# Power_Protection.net
KiCad netlist of a schematic drawn in Altium Designer
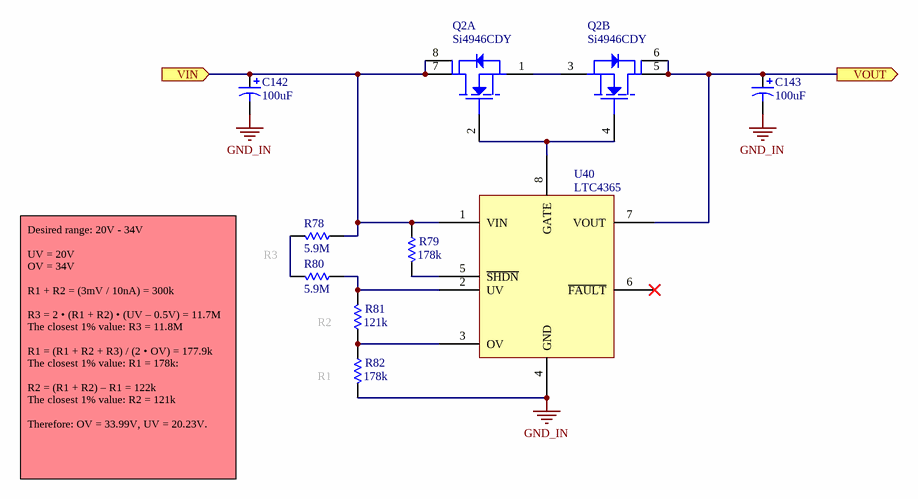
[diagram p0: Power_Protection.SchDoc]

(export (version "E")
  (design (tool "Eeschema 10.0.6"))
  (components
    (comp (ref "C142")
      (value "100uF")
      (footprint "AMDC:CAP - UWT1V101MCL1GS")
      (description "Polarized Capacitor (Radial)")
      (fields (field (name "Comment") "Cap Pol1"))
      (libsource (lib "Miscellaneous Devices") (part "Cap Pol1"))
    )
    (comp (ref "C143")
      (value "100uF")
      (footprint "AMDC:CAP - UWT1V101MCL1GS")
      (description "Polarized Capacitor (Radial)")
      (fields (field (name "Comment") "Cap Pol1"))
      (libsource (lib "Miscellaneous Devices") (part "Cap Pol1"))
    )
    (comp (ref "Q2")
      (value "Si4946CDY")
      (footprint "AMDC:SOIC127P600X175-8N")
      (description "MOSFET N-CHAN DUAL 60V SO-8")
      (libsource (lib "AMDC") (part "SI4946CDY-T1-GE3"))
    )
    (comp (ref "R78")
      (value "5.9M")
      (footprint "AMDC:0603-RES")
      (description "Resistor")
      (libsource (lib "AMDC") (part "Resistor"))
    )
    (comp (ref "R79")
      (value "178k")
      (footprint "AMDC:0603-RES")
      (description "Resistor")
      (libsource (lib "AMDC") (part "Resistor"))
    )
    (comp (ref "R80")
      (value "5.9M")
      (footprint "AMDC:0603-RES")
      (description "Resistor")
      (libsource (lib "AMDC") (part "Resistor"))
    )
    (comp (ref "R81")
      (value "121k")
      (footprint "AMDC:0603-RES")
      (description "Resistor")
      (libsource (lib "AMDC") (part "Resistor"))
    )
    (comp (ref "R82")
      (value "178k")
      (footprint "AMDC:0603-RES")
      (description "Resistor")
      (libsource (lib "AMDC") (part "Resistor"))
    )
    (comp (ref "U40")
      (value "LTC4365")
      (footprint "AMDC:TSOP65P280X100-8N")
      (description "IC OVERVOLTAGE PROT TSOT23-8")
      (libsource (lib "AMDC") (part "LTC4365CTS8#TRMPBF"))
    )
  )
  (nets
    (net (code "1") (name "/VIN") (class "Default")
      (node (ref "C142") (pin "1") (pinfunction "1_1") (pintype "passive"))
      (node (ref "Q2") (pin "7") (pinfunction "D1_7") (pintype "passive"))
      (node (ref "Q2") (pin "8") (pinfunction "D1_8") (pintype "passive"))
      (node (ref "R78") (pin "1") (pinfunction "1_1") (pintype "passive"))
      (node (ref "R79") (pin "1") (pinfunction "1_1") (pintype "passive"))
      (node (ref "U40") (pin "1") (pinfunction "VIN_1") (pintype "passive"))
    )
    (net (code "2") (name "/VOUT") (class "Default")
      (node (ref "C143") (pin "1") (pinfunction "1_1") (pintype "passive"))
      (node (ref "Q2") (pin "5") (pinfunction "D2_5") (pintype "passive"))
      (node (ref "Q2") (pin "6") (pinfunction "D2_6") (pintype "passive"))
      (node (ref "U40") (pin "7") (pinfunction "VOUT_7") (pintype "passive"))
    )
    (net (code "3") (name "GND_IN") (class "Default")
      (node (ref "C142") (pin "2") (pinfunction "2_2") (pintype "passive"))
      (node (ref "C143") (pin "2") (pinfunction "2_2") (pintype "passive"))
      (node (ref "R82") (pin "2") (pinfunction "2_2") (pintype "passive"))
      (node (ref "U40") (pin "4") (pinfunction "GND_4") (pintype "passive"))
    )
    (net (code "4") (name "Net-(Q2A-G1)") (class "Default")
      (node (ref "Q2") (pin "2") (pinfunction "G1_2") (pintype "passive"))
      (node (ref "Q2") (pin "4") (pinfunction "G2_4") (pintype "passive"))
      (node (ref "U40") (pin "8") (pinfunction "GATE_8") (pintype "passive"))
    )
    (net (code "5") (name "Net-(Q2A-S1)") (class "Default")
      (node (ref "Q2") (pin "1") (pinfunction "S1_1") (pintype "passive"))
      (node (ref "Q2") (pin "3") (pinfunction "S2_3") (pintype "passive"))
    )
    (net (code "6") (name "Net-(R78-Pad2)") (class "Default")
      (node (ref "R78") (pin "2") (pinfunction "2_2") (pintype "passive"))
      (node (ref "R80") (pin "2") (pinfunction "2_2") (pintype "passive"))
    )
    (net (code "7") (name "Net-(U40-OV)") (class "Default")
      (node (ref "R81") (pin "1") (pinfunction "1_1") (pintype "passive"))
      (node (ref "R82") (pin "1") (pinfunction "1_1") (pintype "passive"))
      (node (ref "U40") (pin "3") (pinfunction "OV_3") (pintype "passive"))
    )
    (net (code "8") (name "Net-(U40-UV)") (class "Default")
      (node (ref "R80") (pin "1") (pinfunction "1_1") (pintype "passive"))
      (node (ref "R81") (pin "2") (pinfunction "2_2") (pintype "passive"))
      (node (ref "U40") (pin "2") (pinfunction "UV_2") (pintype "passive"))
    )
    (net (code "9") (name "Net-(U40-~{SHDN})") (class "Default")
      (node (ref "R79") (pin "2") (pinfunction "2_2") (pintype "passive"))
      (node (ref "U40") (pin "5") (pinfunction "~{SHDN}_5") (pintype "passive"))
    )
    (net (code "10") (name "unconnected-(U40-~{FAULT}-Pad6)") (class "Default")
      (node (ref "U40") (pin "6") (pinfunction "~{FAULT}_6") (pintype "passive+no_connect"))
    )
  )
)
